# mpc57_mcupower.net
KiCad netlist of a schematic drawn in Altium Designer
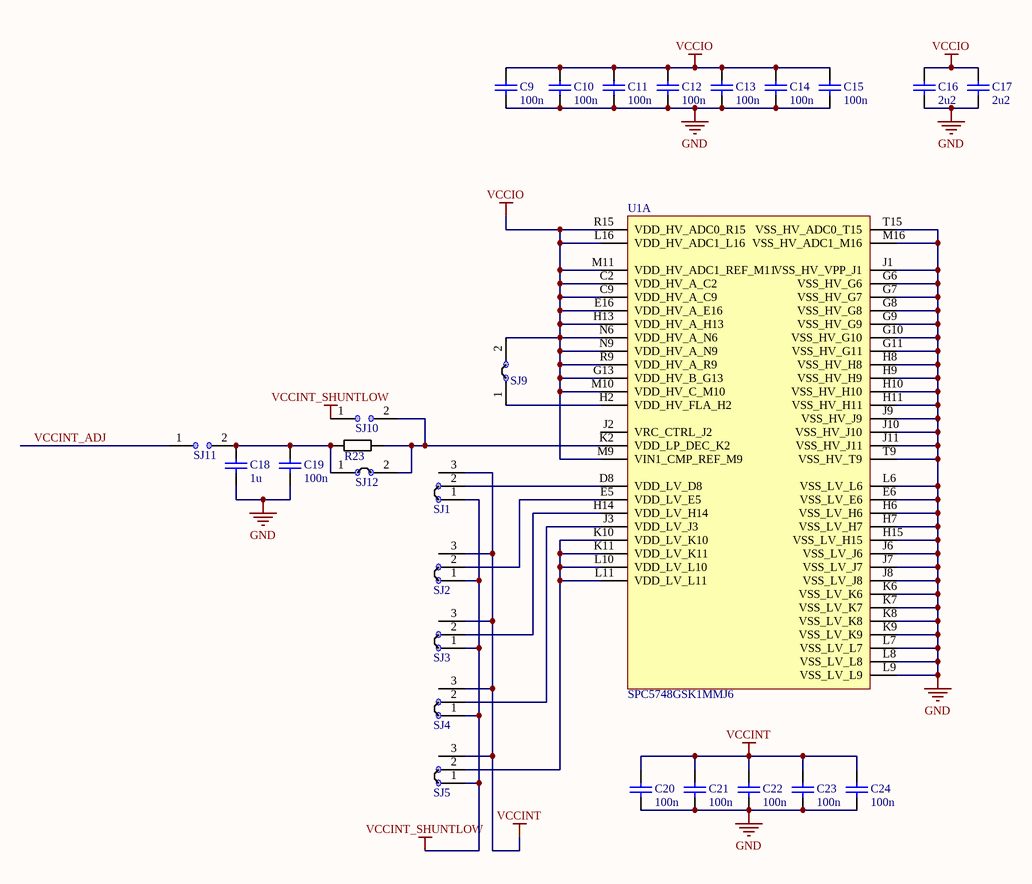
[diagram p0: mpc57_mcupower.SchDoc]

(export (version "E")
  (design (tool "Eeschema 10.0.6"))
  (components
    (comp (ref "C9")
      (value "100n")
      (footprint "CAPC0402_M")
      (description "100n, 0402")
      (fields (field (name "PART NUMBER") "CCHIP-100n-0402"))
      (libsource (lib "NewAE_AltiumLib") (part "CAP"))
    )
    (comp (ref "C10")
      (value "100n")
      (footprint "CAPC0402_M")
      (description "100n, 0402")
      (fields (field (name "PART NUMBER") "CCHIP-100n-0402"))
      (libsource (lib "NewAE_AltiumLib") (part "CAP"))
    )
    (comp (ref "C11")
      (value "100n")
      (footprint "CAPC0402_M")
      (description "100n, 0402")
      (fields (field (name "PART NUMBER") "CCHIP-100n-0402"))
      (libsource (lib "NewAE_AltiumLib") (part "CAP"))
    )
    (comp (ref "C12")
      (value "100n")
      (footprint "CAPC0402_M")
      (description "100n, 0402")
      (fields (field (name "PART NUMBER") "CCHIP-100n-0402"))
      (libsource (lib "NewAE_AltiumLib") (part "CAP"))
    )
    (comp (ref "C13")
      (value "100n")
      (footprint "CAPC0402_M")
      (description "100n, 0402")
      (fields (field (name "PART NUMBER") "CCHIP-100n-0402"))
      (libsource (lib "NewAE_AltiumLib") (part "CAP"))
    )
    (comp (ref "C14")
      (value "100n")
      (footprint "CAPC0402_M")
      (description "100n, 0402")
      (fields (field (name "PART NUMBER") "CCHIP-100n-0402"))
      (libsource (lib "NewAE_AltiumLib") (part "CAP"))
    )
    (comp (ref "C15")
      (value "100n")
      (footprint "CAPC0402_M")
      (description "100n, 0402")
      (fields (field (name "PART NUMBER") "CCHIP-100n-0402"))
      (libsource (lib "NewAE_AltiumLib") (part "CAP"))
    )
    (comp (ref "C16")
      (value "2u2")
      (footprint "CAPC0603_M")
      (description "2u2, 0603")
      (fields (field (name "PART NUMBER") "CCHIP-2u2-0603"))
      (libsource (lib "NewAE_AltiumLib") (part "CAP"))
    )
    (comp (ref "C17")
      (value "2u2")
      (footprint "CAPC0603_M")
      (description "2u2, 0603")
      (fields (field (name "PART NUMBER") "CCHIP-2u2-0603"))
      (libsource (lib "NewAE_AltiumLib") (part "CAP"))
    )
    (comp (ref "C18")
      (value "1u")
      (footprint "CAPC0603_M")
      (description "1u, 0603")
      (fields (field (name "PART NUMBER") "CCHIP-1u-0603"))
      (libsource (lib "NewAE_AltiumLib") (part "CAP"))
    )
    (comp (ref "C19")
      (value "100n")
      (footprint "CAPC0402_M")
      (description "100n, 0402")
      (fields (field (name "PART NUMBER") "CCHIP-100n-0402"))
      (libsource (lib "NewAE_AltiumLib") (part "CAP"))
    )
    (comp (ref "C20")
      (value "100n")
      (footprint "CAPC0402_M")
      (description "100n, 0402")
      (fields (field (name "PART NUMBER") "CCHIP-100n-0402"))
      (libsource (lib "NewAE_AltiumLib") (part "CAP"))
    )
    (comp (ref "C21")
      (value "100n")
      (footprint "CAPC0402_M")
      (description "100n, 0402")
      (fields (field (name "PART NUMBER") "CCHIP-100n-0402"))
      (libsource (lib "NewAE_AltiumLib") (part "CAP"))
    )
    (comp (ref "C22")
      (value "100n")
      (footprint "CAPC0402_M")
      (description "100n, 0402")
      (fields (field (name "PART NUMBER") "CCHIP-100n-0402"))
      (libsource (lib "NewAE_AltiumLib") (part "CAP"))
    )
    (comp (ref "C23")
      (value "100n")
      (footprint "CAPC0402_M")
      (description "100n, 0402")
      (fields (field (name "PART NUMBER") "CCHIP-100n-0402"))
      (libsource (lib "NewAE_AltiumLib") (part "CAP"))
    )
    (comp (ref "C24")
      (value "100n")
      (footprint "CAPC0402_M")
      (description "100n, 0402")
      (fields (field (name "PART NUMBER") "CCHIP-100n-0402"))
      (libsource (lib "NewAE_AltiumLib") (part "CAP"))
    )
    (comp (ref "R23")
      (value "1R0")
      (footprint "RESC1608X55N")
      (description "1R0 res, 0603, 1%, 1/10W")
      (fields (field (name "PART NUMBER") "RCHIP-1R0-0603") (field (name "TOLERANCE") "1%"))
      (libsource (lib "NewAE_AltiumLib") (part "RES-EU"))
    )
    (comp (ref "SJ1")
      (value "NC")
      (footprint "SJ_3S_NC12")
      (description "Solder Jumper, NC")
      (fields (field (name "PART NUMBER") "SJ_3S_12JMP"))
      (libsource (lib "NewAE_AltiumLib") (part "SJ_3S_12JMP"))
    )
    (comp (ref "SJ2")
      (value "NC")
      (footprint "SJ_3S_NC12")
      (description "Solder Jumper, NC")
      (fields (field (name "PART NUMBER") "SJ_3S_12JMP"))
      (libsource (lib "NewAE_AltiumLib") (part "SJ_3S_12JMP"))
    )
    (comp (ref "SJ3")
      (value "NC")
      (footprint "SJ_3S_NC12")
      (description "Solder Jumper, NC")
      (fields (field (name "PART NUMBER") "SJ_3S_12JMP"))
      (libsource (lib "NewAE_AltiumLib") (part "SJ_3S_12JMP"))
    )
    (comp (ref "SJ4")
      (value "NC")
      (footprint "SJ_3S_NC12")
      (description "Solder Jumper, NC")
      (fields (field (name "PART NUMBER") "SJ_3S_12JMP"))
      (libsource (lib "NewAE_AltiumLib") (part "SJ_3S_12JMP"))
    )
    (comp (ref "SJ5")
      (value "NC")
      (footprint "SJ_3S_NC12")
      (description "Solder Jumper, NC")
      (fields (field (name "PART NUMBER") "SJ_3S_12JMP"))
      (libsource (lib "NewAE_AltiumLib") (part "SJ_3S_12JMP"))
    )
    (comp (ref "SJ9")
      (value "NC")
      (footprint "SJ_2S_NC")
      (description "Solder Jumper, NC")
      (fields (field (name "PART NUMBER") "SJ_2S"))
      (libsource (lib "NewAE_AltiumLib") (part "SJ_2S"))
    )
    (comp (ref "SJ10")
      (value "NO")
      (footprint "SJ_2S_NO")
      (description "Solder Jumper, NO")
      (fields (field (name "PART NUMBER") "SJ_2S_NO"))
      (libsource (lib "NewAE_AltiumLib") (part "SJ_2S_NO"))
    )
    (comp (ref "SJ11")
      (value "NO")
      (footprint "SJ_2S_NO")
      (description "Solder Jumper, NO")
      (fields (field (name "PART NUMBER") "SJ_2S_NO"))
      (libsource (lib "NewAE_AltiumLib") (part "SJ_2S_NO"))
    )
    (comp (ref "SJ12")
      (value "NC")
      (footprint "SJ_2S_NC")
      (description "Solder Jumper, NC")
      (fields (field (name "PART NUMBER") "SJ_2S"))
      (libsource (lib "NewAE_AltiumLib") (part "SJ_2S"))
    )
    (comp (ref "U1")
      (value "SPC5748GSK1MMJ6")
      (footprint "NewAE_AltiumLib:BGA256C100P16X16_1700X1700X170")
      (description "Freescale 32-bit MCU, Triple core, 6MB Flash, 160MHz, -40/+125degC, Automotive Qualified, BGA 256")
      (libsource (lib "NewAE_AltiumLib") (part "SPC5748GSK1MMJ6"))
    )
  )
  (nets
    (net (code "1") (name "/VCCINT_ADJ") (class "Default")
      (node (ref "SJ11") (pin "1") (pinfunction "1_1") (pintype "passive"))
    )
    (net (code "2") (name "GND") (class "Default")
      (node (ref "C10") (pin "2") (pinfunction "2_2") (pintype "passive"))
      (node (ref "C11") (pin "2") (pinfunction "2_2") (pintype "passive"))
      (node (ref "C12") (pin "2") (pinfunction "2_2") (pintype "passive"))
      (node (ref "C13") (pin "2") (pinfunction "2_2") (pintype "passive"))
      (node (ref "C14") (pin "2") (pinfunction "2_2") (pintype "passive"))
      (node (ref "C15") (pin "2") (pinfunction "2_2") (pintype "passive"))
      (node (ref "C16") (pin "2") (pinfunction "2_2") (pintype "passive"))
      (node (ref "C17") (pin "2") (pinfunction "2_2") (pintype "passive"))
      (node (ref "C18") (pin "2") (pinfunction "2_2") (pintype "passive"))
      (node (ref "C19") (pin "2") (pinfunction "2_2") (pintype "passive"))
      (node (ref "C20") (pin "2") (pinfunction "2_2") (pintype "passive"))
      (node (ref "C21") (pin "2") (pinfunction "2_2") (pintype "passive"))
      (node (ref "C22") (pin "2") (pinfunction "2_2") (pintype "passive"))
      (node (ref "C23") (pin "2") (pinfunction "2_2") (pintype "passive"))
      (node (ref "C24") (pin "2") (pinfunction "2_2") (pintype "passive"))
      (node (ref "C9") (pin "2") (pinfunction "2_2") (pintype "passive"))
      (node (ref "U1") (pin "E6") (pinfunction "VSS_LV_E6_E6") (pintype "power_in"))
      (node (ref "U1") (pin "G10") (pinfunction "VSS_HV_G10_G10") (pintype "power_in"))
      (node (ref "U1") (pin "G11") (pinfunction "VSS_HV_G11_G11") (pintype "power_in"))
      (node (ref "U1") (pin "G6") (pinfunction "VSS_HV_G6_G6") (pintype "power_in"))
      (node (ref "U1") (pin "G7") (pinfunction "VSS_HV_G7_G7") (pintype "power_in"))
      (node (ref "U1") (pin "G8") (pinfunction "VSS_HV_G8_G8") (pintype "power_in"))
      (node (ref "U1") (pin "G9") (pinfunction "VSS_HV_G9_G9") (pintype "power_in"))
      (node (ref "U1") (pin "H10") (pinfunction "VSS_HV_H10_H10") (pintype "power_in"))
      (node (ref "U1") (pin "H11") (pinfunction "VSS_HV_H11_H11") (pintype "power_in"))
      (node (ref "U1") (pin "H15") (pinfunction "VSS_LV_H15_H15") (pintype "power_in"))
      (node (ref "U1") (pin "H6") (pinfunction "VSS_LV_H6_H6") (pintype "power_in"))
      (node (ref "U1") (pin "H7") (pinfunction "VSS_LV_H7_H7") (pintype "power_in"))
      (node (ref "U1") (pin "H8") (pinfunction "VSS_HV_H8_H8") (pintype "power_in"))
      (node (ref "U1") (pin "H9") (pinfunction "VSS_HV_H9_H9") (pintype "power_in"))
      (node (ref "U1") (pin "J1") (pinfunction "VSS_HV_VPP_J1_J1") (pintype "power_in"))
      (node (ref "U1") (pin "J10") (pinfunction "VSS_HV_J10_J10") (pintype "power_in"))
      (node (ref "U1") (pin "J11") (pinfunction "VSS_HV_J11_J11") (pintype "power_in"))
      (node (ref "U1") (pin "J6") (pinfunction "VSS_LV_J6_J6") (pintype "power_in"))
      (node (ref "U1") (pin "J7") (pinfunction "VSS_LV_J7_J7") (pintype "power_in"))
      (node (ref "U1") (pin "J8") (pinfunction "VSS_LV_J8_J8") (pintype "power_in"))
      (node (ref "U1") (pin "J9") (pinfunction "VSS_HV_J9_J9") (pintype "power_in"))
      (node (ref "U1") (pin "K6") (pinfunction "VSS_LV_K6_K6") (pintype "power_in"))
      (node (ref "U1") (pin "K7") (pinfunction "VSS_LV_K7_K7") (pintype "power_in"))
      (node (ref "U1") (pin "K8") (pinfunction "VSS_LV_K8_K8") (pintype "power_in"))
      (node (ref "U1") (pin "K9") (pinfunction "VSS_LV_K9_K9") (pintype "power_in"))
      (node (ref "U1") (pin "L6") (pinfunction "VSS_LV_L6_L6") (pintype "power_in"))
      (node (ref "U1") (pin "L7") (pinfunction "VSS_LV_L7_L7") (pintype "power_in"))
      (node (ref "U1") (pin "L8") (pinfunction "VSS_LV_L8_L8") (pintype "power_in"))
      (node (ref "U1") (pin "L9") (pinfunction "VSS_LV_L9_L9") (pintype "power_in"))
      (node (ref "U1") (pin "M16") (pinfunction "VSS_HV_ADC1_M16_M16") (pintype "power_in"))
      (node (ref "U1") (pin "T15") (pinfunction "VSS_HV_ADC0_T15_T15") (pintype "power_in"))
      (node (ref "U1") (pin "T9") (pinfunction "VSS_HV_T9_T9") (pintype "power_in"))
    )
    (net (code "3") (name "Net-(C18-Pad1)") (class "Default")
      (node (ref "C18") (pin "1") (pinfunction "1_1") (pintype "passive"))
      (node (ref "C19") (pin "1") (pinfunction "1_1") (pintype "passive"))
      (node (ref "R23") (pin "1") (pinfunction "1_1") (pintype "passive"))
      (node (ref "SJ11") (pin "2") (pinfunction "2_2") (pintype "passive"))
      (node (ref "SJ12") (pin "1") (pinfunction "1_1") (pintype "passive"))
    )
    (net (code "4") (name "Net-(U1A-VDD_HV_FLA_H2)") (class "Default")
      (node (ref "SJ9") (pin "1") (pinfunction "1_1") (pintype "passive"))
      (node (ref "U1") (pin "H2") (pinfunction "VDD_HV_FLA_H2_H2") (pintype "power_in"))
    )
    (net (code "5") (name "Net-(U1A-VDD_LP_DEC_K2)") (class "Default")
      (node (ref "R23") (pin "2") (pinfunction "2_2") (pintype "passive"))
      (node (ref "SJ10") (pin "2") (pinfunction "2_2") (pintype "passive"))
      (node (ref "SJ12") (pin "2") (pinfunction "2_2") (pintype "passive"))
      (node (ref "U1") (pin "K2") (pinfunction "VDD_LP_DEC_K2_K2") (pintype "power_in"))
    )
    (net (code "6") (name "Net-(U1A-VDD_LV_D8)") (class "Default")
      (node (ref "SJ1") (pin "2") (pinfunction "2_2") (pintype "passive"))
      (node (ref "U1") (pin "D8") (pinfunction "VDD_LV_D8_D8") (pintype "power_in"))
    )
    (net (code "7") (name "Net-(U1A-VDD_LV_E5)") (class "Default")
      (node (ref "SJ2") (pin "2") (pinfunction "2_2") (pintype "passive"))
      (node (ref "U1") (pin "E5") (pinfunction "VDD_LV_E5_E5") (pintype "power_in"))
    )
    (net (code "8") (name "Net-(U1A-VDD_LV_H14)") (class "Default")
      (node (ref "SJ3") (pin "2") (pinfunction "2_2") (pintype "passive"))
      (node (ref "U1") (pin "H14") (pinfunction "VDD_LV_H14_H14") (pintype "power_in"))
    )
    (net (code "9") (name "Net-(U1A-VDD_LV_J3)") (class "Default")
      (node (ref "SJ4") (pin "2") (pinfunction "2_2") (pintype "passive"))
      (node (ref "U1") (pin "J3") (pinfunction "VDD_LV_J3_J3") (pintype "power_in"))
    )
    (net (code "10") (name "Net-(U1A-VDD_LV_K10)") (class "Default")
      (node (ref "SJ5") (pin "2") (pinfunction "2_2") (pintype "passive"))
      (node (ref "U1") (pin "K10") (pinfunction "VDD_LV_K10_K10") (pintype "power_in"))
      (node (ref "U1") (pin "K11") (pinfunction "VDD_LV_K11_K11") (pintype "power_in"))
      (node (ref "U1") (pin "L10") (pinfunction "VDD_LV_L10_L10") (pintype "power_in"))
      (node (ref "U1") (pin "L11") (pinfunction "VDD_LV_L11_L11") (pintype "power_in"))
    )
    (net (code "11") (name "VCCINT") (class "Default")
      (node (ref "C20") (pin "1") (pinfunction "1_1") (pintype "passive"))
      (node (ref "C21") (pin "1") (pinfunction "1_1") (pintype "passive"))
      (node (ref "C22") (pin "1") (pinfunction "1_1") (pintype "passive"))
      (node (ref "C23") (pin "1") (pinfunction "1_1") (pintype "passive"))
      (node (ref "C24") (pin "1") (pinfunction "1_1") (pintype "passive"))
      (node (ref "SJ1") (pin "3") (pinfunction "3_3") (pintype "passive"))
      (node (ref "SJ2") (pin "3") (pinfunction "3_3") (pintype "passive"))
      (node (ref "SJ3") (pin "3") (pinfunction "3_3") (pintype "passive"))
      (node (ref "SJ4") (pin "3") (pinfunction "3_3") (pintype "passive"))
      (node (ref "SJ5") (pin "3") (pinfunction "3_3") (pintype "passive"))
    )
    (net (code "12") (name "VCCINT_SHUNTLOW") (class "Default")
      (node (ref "SJ1") (pin "1") (pinfunction "1_1") (pintype "passive"))
      (node (ref "SJ10") (pin "1") (pinfunction "1_1") (pintype "passive"))
      (node (ref "SJ2") (pin "1") (pinfunction "1_1") (pintype "passive"))
      (node (ref "SJ3") (pin "1") (pinfunction "1_1") (pintype "passive"))
      (node (ref "SJ4") (pin "1") (pinfunction "1_1") (pintype "passive"))
      (node (ref "SJ5") (pin "1") (pinfunction "1_1") (pintype "passive"))
    )
    (net (code "13") (name "VCCIO") (class "Default")
      (node (ref "C10") (pin "1") (pinfunction "1_1") (pintype "passive"))
      (node (ref "C11") (pin "1") (pinfunction "1_1") (pintype "passive"))
      (node (ref "C12") (pin "1") (pinfunction "1_1") (pintype "passive"))
      (node (ref "C13") (pin "1") (pinfunction "1_1") (pintype "passive"))
      (node (ref "C14") (pin "1") (pinfunction "1_1") (pintype "passive"))
      (node (ref "C15") (pin "1") (pinfunction "1_1") (pintype "passive"))
      (node (ref "C16") (pin "1") (pinfunction "1_1") (pintype "passive"))
      (node (ref "C17") (pin "1") (pinfunction "1_1") (pintype "passive"))
      (node (ref "C9") (pin "1") (pinfunction "1_1") (pintype "passive"))
      (node (ref "SJ9") (pin "2") (pinfunction "2_2") (pintype "passive"))
      (node (ref "U1") (pin "C2") (pinfunction "VDD_HV_A_C2_C2") (pintype "power_in"))
      (node (ref "U1") (pin "C9") (pinfunction "VDD_HV_A_C9_C9") (pintype "power_in"))
      (node (ref "U1") (pin "E16") (pinfunction "VDD_HV_A_E16_E16") (pintype "power_in"))
      (node (ref "U1") (pin "G13") (pinfunction "VDD_HV_B_G13_G13") (pintype "power_in"))
      (node (ref "U1") (pin "H13") (pinfunction "VDD_HV_A_H13_H13") (pintype "power_in"))
      (node (ref "U1") (pin "L16") (pinfunction "VDD_HV_ADC1_L16_L16") (pintype "power_in"))
      (node (ref "U1") (pin "M10") (pinfunction "VDD_HV_C_M10_M10") (pintype "power_in"))
      (node (ref "U1") (pin "M11") (pinfunction "VDD_HV_ADC1_REF_M11_M11") (pintype "power_in"))
      (node (ref "U1") (pin "M9") (pinfunction "VIN1_CMP_REF_M9_M9") (pintype "power_in"))
      (node (ref "U1") (pin "N6") (pinfunction "VDD_HV_A_N6_N6") (pintype "power_in"))
      (node (ref "U1") (pin "N9") (pinfunction "VDD_HV_A_N9_N9") (pintype "power_in"))
      (node (ref "U1") (pin "R15") (pinfunction "VDD_HV_ADC0_R15_R15") (pintype "power_in"))
      (node (ref "U1") (pin "R9") (pinfunction "VDD_HV_A_R9_R9") (pintype "power_in"))
    )
    (net (code "14") (name "unconnected-(U1A-VRC_CTRL_J2-PadJ2)") (class "Default")
      (node (ref "U1") (pin "J2") (pinfunction "VRC_CTRL_J2_J2") (pintype "power_in"))
    )
  )
)
